# STM32F4_Schematics.net
KiCad netlist of a schematic drawn in Altium Designer
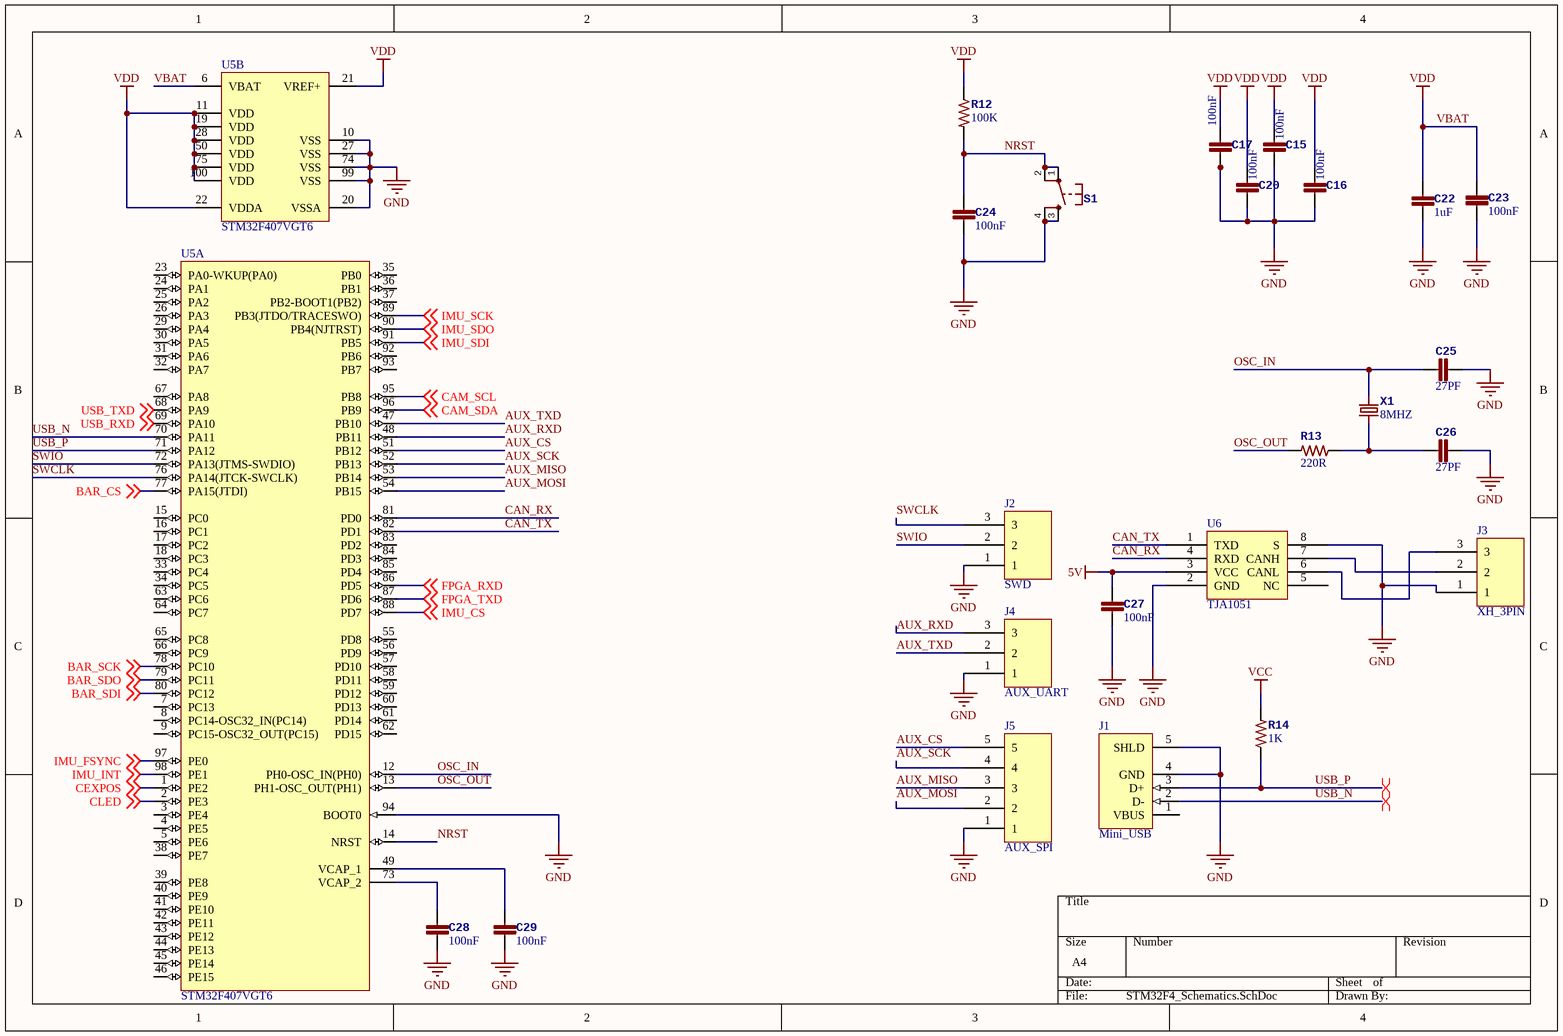
[diagram p0: STM32F4_Schematics.SchDoc]

(export (version "E")
  (design (tool "Eeschema 10.0.6"))
  (components
    (comp (ref "C15")
      (value "100nF")
      (footprint "_0805")
      (fields (field (name "Comment") "Cap"))
      (libsource (lib "") (part "Cap_1_1"))
    )
    (comp (ref "C16")
      (value "100nF")
      (footprint "_0805")
      (fields (field (name "Comment") "Cap"))
      (libsource (lib "") (part "Cap_1_1"))
    )
    (comp (ref "C17")
      (value "100nF")
      (footprint "_0805")
      (fields (field (name "Comment") "Cap"))
      (libsource (lib "") (part "Cap_1_1"))
    )
    (comp (ref "C20")
      (value "100nF")
      (footprint "_0805")
      (fields (field (name "Comment") "Cap"))
      (libsource (lib "") (part "Cap_1_1"))
    )
    (comp (ref "C22")
      (value "1uF")
      (footprint "_0805")
      (fields (field (name "Comment") "Cap"))
      (libsource (lib "") (part "Cap_1_1"))
    )
    (comp (ref "C23")
      (value "100nF")
      (footprint "_0805")
      (fields (field (name "Comment") "Cap"))
      (libsource (lib "") (part "Cap_1_1"))
    )
    (comp (ref "C24")
      (value "100nF")
      (footprint "_0805")
      (fields (field (name "Comment") "Cap"))
      (libsource (lib "") (part "Cap_1_2"))
    )
    (comp (ref "C25")
      (value "27PF")
      (footprint "_0805")
      (fields (field (name "Comment") "Cap"))
      (libsource (lib "Passives_Integrated_Library") (part "Cap_1"))
    )
    (comp (ref "C26")
      (value "27PF")
      (footprint "_0805")
      (fields (field (name "Comment") "Cap"))
      (libsource (lib "Passives_Integrated_Library") (part "Cap_1"))
    )
    (comp (ref "C27")
      (value "100nF")
      (footprint "_0805")
      (fields (field (name "Comment") "Cap"))
      (libsource (lib "") (part "Cap_1_1"))
    )
    (comp (ref "C28")
      (value "100nF")
      (footprint "_0805")
      (fields (field (name "Comment") "Cap"))
      (libsource (lib "") (part "Cap_1_1"))
    )
    (comp (ref "C29")
      (value "100nF")
      (footprint "_0805")
      (fields (field (name "Comment") "Cap"))
      (libsource (lib "") (part "Cap_1_1"))
    )
    (comp (ref "J1")
      (value "Mini_USB")
      (footprint "My_USB")
      (description "USB 2.0, Right Angle, SMT, B Type, Receptacle, 5 Position, Black")
      (fields (field (name "PUBLISHER") "Altium Limited"))
      (libsource (lib "PC_Connectors_Integrated_Library") (part "Mini_USB"))
    )
    (comp (ref "J2")
      (value "SWD")
      (footprint "XH_3PIN")
      (libsource (lib "Others_Integrated_Library") (part "XH_3PIN"))
    )
    (comp (ref "J3")
      (value "XH_3PIN")
      (footprint "XH_3PIN")
      (libsource (lib "Others_Integrated_Library") (part "XH_3PIN"))
    )
    (comp (ref "J4")
      (value "AUX_UART")
      (footprint "XH_3PIN")
      (libsource (lib "Others_Integrated_Library") (part "XH_3PIN"))
    )
    (comp (ref "J5")
      (value "AUX_SPI")
      (footprint "XH_5PIN")
      (libsource (lib "Others_Integrated_Library") (part "XH_5PIN"))
    )
    (comp (ref "R12")
      (value "100K")
      (footprint "_0603")
      (fields (field (name "Comment") "Resistor"))
      (libsource (lib "Passives_Integrated_Library") (part "Resistor"))
    )
    (comp (ref "R13")
      (value "220R")
      (footprint "_0603")
      (fields (field (name "Comment") "Resistor"))
      (libsource (lib "Passives_Integrated_Library") (part "Resistor"))
    )
    (comp (ref "R14")
      (value "1K")
      (footprint "_0603")
      (fields (field (name "Comment") "Resistor"))
      (libsource (lib "Passives_Integrated_Library") (part "Resistor"))
    )
    (comp (ref "S1")
      (value "PushButton-4Pin")
      (footprint "_TACTILE_SWITCH_PTH_6.0MM")
      (libsource (lib "Miscellaneous_Integrated_Library") (part "PushButton-4Pin"))
    )
    (comp (ref "U5")
      (value "STM32F407VGT6")
      (footprint "STM-LQFP100_N")
      (fields (field (name "MANUFACTURER") "STMicroelectronics"))
      (libsource (lib "STMicroelectronics STM32 F4") (part "STM32F407VGT6"))
    )
    (comp (ref "U6")
      (value "TJA1051")
      (footprint "SO-8N")
      (libsource (lib "Transievers_Integrated_Library") (part "TJA1051"))
    )
    (comp (ref "X1")
      (value "8MHZ")
      (footprint "_CRYSTAL-HC49UP")
      (fields (field (name "Comment") "Crystal_1"))
      (libsource (lib "Passives_Integrated_Library") (part "Crystal_1"))
    )
  )
  (nets
    (net (code "1") (name "/AUX_CS") (class "Default")
      (node (ref "J5") (pin "5") (pinfunction "5_5") (pintype "passive"))
      (node (ref "U5") (pin "51") (pinfunction "PB12_51") (pintype "bidirectional"))
    )
    (net (code "2") (name "/AUX_MISO") (class "Default")
      (node (ref "J5") (pin "3") (pinfunction "3_3") (pintype "passive"))
      (node (ref "U5") (pin "53") (pinfunction "PB14_53") (pintype "bidirectional"))
    )
    (net (code "3") (name "/AUX_MOSI") (class "Default")
      (node (ref "J5") (pin "2") (pinfunction "2_2") (pintype "passive"))
      (node (ref "U5") (pin "54") (pinfunction "PB15_54") (pintype "bidirectional"))
    )
    (net (code "4") (name "/AUX_RXD") (class "Default")
      (node (ref "J4") (pin "3") (pinfunction "3_3") (pintype "passive"))
      (node (ref "U5") (pin "48") (pinfunction "PB11_48") (pintype "bidirectional"))
    )
    (net (code "5") (name "/AUX_SCK") (class "Default")
      (node (ref "J5") (pin "4") (pinfunction "4_4") (pintype "passive"))
      (node (ref "U5") (pin "52") (pinfunction "PB13_52") (pintype "bidirectional"))
    )
    (net (code "6") (name "/AUX_TXD") (class "Default")
      (node (ref "J4") (pin "2") (pinfunction "2_2") (pintype "passive"))
      (node (ref "U5") (pin "47") (pinfunction "PB10_47") (pintype "bidirectional"))
    )
    (net (code "7") (name "/CAN_RX") (class "Default")
      (node (ref "U5") (pin "81") (pinfunction "PD0_81") (pintype "bidirectional"))
      (node (ref "U6") (pin "4") (pinfunction "RXD_4") (pintype "passive"))
    )
    (net (code "8") (name "/CAN_TX") (class "Default")
      (node (ref "U5") (pin "82") (pinfunction "PD1_82") (pintype "bidirectional"))
      (node (ref "U6") (pin "1") (pinfunction "TXD_1") (pintype "passive"))
    )
    (net (code "9") (name "/NRST") (class "Default")
      (node (ref "C24") (pin "1") (pinfunction "1_1") (pintype "passive"))
      (node (ref "R12") (pin "2") (pinfunction "2_2") (pintype "passive"))
      (node (ref "S1") (pin "1") (pinfunction "1_1") (pintype "passive"))
      (node (ref "S1") (pin "2") (pinfunction "2_2") (pintype "passive"))
      (node (ref "U5") (pin "14") (pinfunction "NRST_14") (pintype "bidirectional"))
    )
    (net (code "10") (name "/OSC_IN") (class "Default")
      (node (ref "C25") (pin "1") (pinfunction "1_1") (pintype "passive"))
      (node (ref "U5") (pin "12") (pinfunction "PH0-OSC_IN(PH0)_12") (pintype "bidirectional"))
      (node (ref "X1") (pin "2") (pinfunction "2_2") (pintype "passive"))
    )
    (net (code "11") (name "/OSC_OUT") (class "Default")
      (node (ref "R13") (pin "2") (pinfunction "2_2") (pintype "passive"))
      (node (ref "U5") (pin "13") (pinfunction "PH1-OSC_OUT(PH1)_13") (pintype "bidirectional"))
    )
    (net (code "12") (name "/SWCLK") (class "Default")
      (node (ref "J2") (pin "3") (pinfunction "3_3") (pintype "passive"))
      (node (ref "U5") (pin "76") (pinfunction "PA14(JTCK-SWCLK)_76") (pintype "bidirectional"))
    )
    (net (code "13") (name "/SWIO") (class "Default")
      (node (ref "J2") (pin "2") (pinfunction "2_2") (pintype "passive"))
      (node (ref "U5") (pin "72") (pinfunction "PA13(JTMS-SWDIO)_72") (pintype "bidirectional"))
    )
    (net (code "14") (name "/USB_N") (class "Default")
      (node (ref "J1") (pin "2") (pinfunction "D-_2") (pintype "input"))
      (node (ref "U5") (pin "70") (pinfunction "PA11_70") (pintype "bidirectional"))
    )
    (net (code "15") (name "/USB_P") (class "Default")
      (node (ref "J1") (pin "3") (pinfunction "D+_3") (pintype "input"))
      (node (ref "R14") (pin "1") (pinfunction "1_1") (pintype "passive"))
      (node (ref "U5") (pin "71") (pinfunction "PA12_71") (pintype "bidirectional"))
    )
    (net (code "16") (name "5V") (class "Default")
      (node (ref "C27") (pin "2") (pinfunction "2_2") (pintype "passive"))
      (node (ref "U6") (pin "3") (pinfunction "VCC_3") (pintype "passive"))
    )
    (net (code "17") (name "BAR_CS") (class "Default")
      (node (ref "U5") (pin "77") (pinfunction "PA15(JTDI)_77") (pintype "bidirectional"))
    )
    (net (code "18") (name "BAR_SCK") (class "Default")
      (node (ref "U5") (pin "78") (pinfunction "PC10_78") (pintype "bidirectional"))
    )
    (net (code "19") (name "BAR_SDI") (class "Default")
      (node (ref "U5") (pin "80") (pinfunction "PC12_80") (pintype "bidirectional"))
    )
    (net (code "20") (name "BAR_SDO") (class "Default")
      (node (ref "U5") (pin "79") (pinfunction "PC11_79") (pintype "bidirectional"))
    )
    (net (code "21") (name "CAM_SCL") (class "Default")
      (node (ref "U5") (pin "95") (pinfunction "PB8_95") (pintype "bidirectional"))
    )
    (net (code "22") (name "CAM_SDA") (class "Default")
      (node (ref "U5") (pin "96") (pinfunction "PB9_96") (pintype "bidirectional"))
    )
    (net (code "23") (name "CEXPOS") (class "Default")
      (node (ref "U5") (pin "1") (pinfunction "PE2_1") (pintype "bidirectional"))
    )
    (net (code "24") (name "CLED") (class "Default")
      (node (ref "U5") (pin "2") (pinfunction "PE3_2") (pintype "bidirectional"))
    )
    (net (code "25") (name "FPGA_RXD") (class "Default")
      (node (ref "U5") (pin "86") (pinfunction "PD5_86") (pintype "bidirectional"))
    )
    (net (code "26") (name "FPGA_TXD") (class "Default")
      (node (ref "U5") (pin "87") (pinfunction "PD6_87") (pintype "bidirectional"))
    )
    (net (code "27") (name "GND") (class "Default")
      (node (ref "C15") (pin "1") (pinfunction "1_1") (pintype "passive"))
      (node (ref "C16") (pin "1") (pinfunction "1_1") (pintype "passive"))
      (node (ref "C17") (pin "1") (pinfunction "1_1") (pintype "passive"))
      (node (ref "C20") (pin "1") (pinfunction "1_1") (pintype "passive"))
      (node (ref "C22") (pin "1") (pinfunction "1_1") (pintype "passive"))
      (node (ref "C23") (pin "1") (pinfunction "1_1") (pintype "passive"))
      (node (ref "C24") (pin "2") (pinfunction "2_2") (pintype "passive"))
      (node (ref "C25") (pin "2") (pinfunction "2_2") (pintype "passive"))
      (node (ref "C26") (pin "2") (pinfunction "2_2") (pintype "passive"))
      (node (ref "C27") (pin "1") (pinfunction "1_1") (pintype "passive"))
      (node (ref "C28") (pin "1") (pinfunction "1_1") (pintype "passive"))
      (node (ref "C29") (pin "1") (pinfunction "1_1") (pintype "passive"))
      (node (ref "J1") (pin "4") (pinfunction "GND_4") (pintype "power_in"))
      (node (ref "J1") (pin "5") (pinfunction "SHLD_5") (pintype "passive"))
      (node (ref "J2") (pin "1") (pinfunction "1_1") (pintype "passive"))
      (node (ref "J3") (pin "1") (pinfunction "1_1") (pintype "passive"))
      (node (ref "J4") (pin "1") (pinfunction "1_1") (pintype "passive"))
      (node (ref "J5") (pin "1") (pinfunction "1_1") (pintype "passive"))
      (node (ref "S1") (pin "3") (pinfunction "3_3") (pintype "passive"))
      (node (ref "S1") (pin "4") (pinfunction "4_4") (pintype "passive"))
      (node (ref "U5") (pin "10") (pinfunction "VSS_10") (pintype "power_in"))
      (node (ref "U5") (pin "20") (pinfunction "VSSA_20") (pintype "power_in"))
      (node (ref "U5") (pin "27") (pinfunction "VSS_27") (pintype "power_in"))
      (node (ref "U5") (pin "74") (pinfunction "VSS_74") (pintype "power_in"))
      (node (ref "U5") (pin "94") (pinfunction "BOOT0_94") (pintype "input"))
      (node (ref "U5") (pin "99") (pinfunction "VSS_99") (pintype "power_in"))
      (node (ref "U6") (pin "2") (pinfunction "GND_2") (pintype "passive"))
      (node (ref "U6") (pin "8") (pinfunction "S_8") (pintype "passive"))
    )
    (net (code "28") (name "IMU_CS") (class "Default")
      (node (ref "U5") (pin "88") (pinfunction "PD7_88") (pintype "bidirectional"))
    )
    (net (code "29") (name "IMU_FSYNC") (class "Default")
      (node (ref "U5") (pin "97") (pinfunction "PE0_97") (pintype "bidirectional"))
    )
    (net (code "30") (name "IMU_INT") (class "Default")
      (node (ref "U5") (pin "98") (pinfunction "PE1_98") (pintype "bidirectional"))
    )
    (net (code "31") (name "IMU_SCK") (class "Default")
      (node (ref "U5") (pin "89") (pinfunction "PB3(JTDO/TRACESWO)_89") (pintype "bidirectional"))
    )
    (net (code "32") (name "IMU_SDI") (class "Default")
      (node (ref "U5") (pin "91") (pinfunction "PB5_91") (pintype "bidirectional"))
    )
    (net (code "33") (name "IMU_SDO") (class "Default")
      (node (ref "U5") (pin "90") (pinfunction "PB4(NJTRST)_90") (pintype "bidirectional"))
    )
    (net (code "34") (name "Net-(C26-Pad1)") (class "Default")
      (node (ref "C26") (pin "1") (pinfunction "1_1") (pintype "passive"))
      (node (ref "R13") (pin "1") (pinfunction "1_1") (pintype "passive"))
      (node (ref "X1") (pin "1") (pinfunction "1_1") (pintype "passive"))
    )
    (net (code "35") (name "Net-(U5A-VCAP_1)") (class "Default")
      (node (ref "C29") (pin "2") (pinfunction "2_2") (pintype "passive"))
      (node (ref "U5") (pin "49") (pinfunction "VCAP_1_49") (pintype "power_in"))
    )
    (net (code "36") (name "Net-(U5A-VCAP_2)") (class "Default")
      (node (ref "C28") (pin "2") (pinfunction "2_2") (pintype "passive"))
      (node (ref "U5") (pin "73") (pinfunction "VCAP_2_73") (pintype "power_in"))
    )
    (net (code "37") (name "Net-(U6-CANH)") (class "Default")
      (node (ref "J3") (pin "2") (pinfunction "2_2") (pintype "passive"))
      (node (ref "U6") (pin "7") (pinfunction "CANH_7") (pintype "passive"))
    )
    (net (code "38") (name "Net-(U6-CANL)") (class "Default")
      (node (ref "J3") (pin "3") (pinfunction "3_3") (pintype "passive"))
      (node (ref "U6") (pin "6") (pinfunction "CANL_6") (pintype "passive"))
    )
    (net (code "39") (name "USB_RXD") (class "Default")
      (node (ref "U5") (pin "69") (pinfunction "PA10_69") (pintype "bidirectional"))
    )
    (net (code "40") (name "USB_TXD") (class "Default")
      (node (ref "U5") (pin "68") (pinfunction "PA9_68") (pintype "bidirectional"))
    )
    (net (code "41") (name "VCC") (class "Default")
      (node (ref "R14") (pin "2") (pinfunction "2_2") (pintype "passive"))
    )
    (net (code "42") (name "VDD") (class "Default")
      (node (ref "C15") (pin "2") (pinfunction "2_2") (pintype "passive"))
      (node (ref "C16") (pin "2") (pinfunction "2_2") (pintype "passive"))
      (node (ref "C17") (pin "2") (pinfunction "2_2") (pintype "passive"))
      (node (ref "C20") (pin "2") (pinfunction "2_2") (pintype "passive"))
      (node (ref "C22") (pin "2") (pinfunction "2_2") (pintype "passive"))
      (node (ref "C23") (pin "2") (pinfunction "2_2") (pintype "passive"))
      (node (ref "R12") (pin "1") (pinfunction "1_1") (pintype "passive"))
      (node (ref "U5") (pin "100") (pinfunction "VDD_100") (pintype "power_in"))
      (node (ref "U5") (pin "11") (pinfunction "VDD_11") (pintype "power_in"))
      (node (ref "U5") (pin "19") (pinfunction "VDD_19") (pintype "power_in"))
      (node (ref "U5") (pin "21") (pinfunction "VREF+_21") (pintype "power_in"))
      (node (ref "U5") (pin "22") (pinfunction "VDDA_22") (pintype "power_in"))
      (node (ref "U5") (pin "28") (pinfunction "VDD_28") (pintype "power_in"))
      (node (ref "U5") (pin "50") (pinfunction "VDD_50") (pintype "power_in"))
      (node (ref "U5") (pin "6") (pinfunction "VBAT_6") (pintype "power_in"))
      (node (ref "U5") (pin "75") (pinfunction "VDD_75") (pintype "power_in"))
    )
    (net (code "43") (name "unconnected-(J1-VBUS-Pad1)") (class "Default")
      (node (ref "J1") (pin "1") (pinfunction "VBUS_1") (pintype "power_in"))
    )
    (net (code "44") (name "unconnected-(U5A-PA0-WKUP(PA0)-Pad23)") (class "Default")
      (node (ref "U5") (pin "23") (pinfunction "PA0-WKUP(PA0)_23") (pintype "bidirectional"))
    )
    (net (code "45") (name "unconnected-(U5A-PA1-Pad24)") (class "Default")
      (node (ref "U5") (pin "24") (pinfunction "PA1_24") (pintype "bidirectional"))
    )
    (net (code "46") (name "unconnected-(U5A-PA2-Pad25)") (class "Default")
      (node (ref "U5") (pin "25") (pinfunction "PA2_25") (pintype "bidirectional"))
    )
    (net (code "47") (name "unconnected-(U5A-PA3-Pad26)") (class "Default")
      (node (ref "U5") (pin "26") (pinfunction "PA3_26") (pintype "bidirectional"))
    )
    (net (code "48") (name "unconnected-(U5A-PA4-Pad29)") (class "Default")
      (node (ref "U5") (pin "29") (pinfunction "PA4_29") (pintype "bidirectional"))
    )
    (net (code "49") (name "unconnected-(U5A-PA5-Pad30)") (class "Default")
      (node (ref "U5") (pin "30") (pinfunction "PA5_30") (pintype "bidirectional"))
    )
    (net (code "50") (name "unconnected-(U5A-PA6-Pad31)") (class "Default")
      (node (ref "U5") (pin "31") (pinfunction "PA6_31") (pintype "bidirectional"))
    )
    (net (code "51") (name "unconnected-(U5A-PA7-Pad32)") (class "Default")
      (node (ref "U5") (pin "32") (pinfunction "PA7_32") (pintype "bidirectional"))
    )
    (net (code "52") (name "unconnected-(U5A-PA8-Pad67)") (class "Default")
      (node (ref "U5") (pin "67") (pinfunction "PA8_67") (pintype "bidirectional"))
    )
    (net (code "53") (name "unconnected-(U5A-PB0-Pad35)") (class "Default")
      (node (ref "U5") (pin "35") (pinfunction "PB0_35") (pintype "bidirectional"))
    )
    (net (code "54") (name "unconnected-(U5A-PB1-Pad36)") (class "Default")
      (node (ref "U5") (pin "36") (pinfunction "PB1_36") (pintype "bidirectional"))
    )
    (net (code "55") (name "unconnected-(U5A-PB2-BOOT1(PB2)-Pad37)") (class "Default")
      (node (ref "U5") (pin "37") (pinfunction "PB2-BOOT1(PB2)_37") (pintype "bidirectional"))
    )
    (net (code "56") (name "unconnected-(U5A-PB6-Pad92)") (class "Default")
      (node (ref "U5") (pin "92") (pinfunction "PB6_92") (pintype "bidirectional"))
    )
    (net (code "57") (name "unconnected-(U5A-PB7-Pad93)") (class "Default")
      (node (ref "U5") (pin "93") (pinfunction "PB7_93") (pintype "bidirectional"))
    )
    (net (code "58") (name "unconnected-(U5A-PC0-Pad15)") (class "Default")
      (node (ref "U5") (pin "15") (pinfunction "PC0_15") (pintype "bidirectional"))
    )
    (net (code "59") (name "unconnected-(U5A-PC1-Pad16)") (class "Default")
      (node (ref "U5") (pin "16") (pinfunction "PC1_16") (pintype "bidirectional"))
    )
    (net (code "60") (name "unconnected-(U5A-PC2-Pad17)") (class "Default")
      (node (ref "U5") (pin "17") (pinfunction "PC2_17") (pintype "bidirectional"))
    )
    (net (code "61") (name "unconnected-(U5A-PC3-Pad18)") (class "Default")
      (node (ref "U5") (pin "18") (pinfunction "PC3_18") (pintype "bidirectional"))
    )
    (net (code "62") (name "unconnected-(U5A-PC4-Pad33)") (class "Default")
      (node (ref "U5") (pin "33") (pinfunction "PC4_33") (pintype "bidirectional"))
    )
    (net (code "63") (name "unconnected-(U5A-PC5-Pad34)") (class "Default")
      (node (ref "U5") (pin "34") (pinfunction "PC5_34") (pintype "bidirectional"))
    )
    (net (code "64") (name "unconnected-(U5A-PC6-Pad63)") (class "Default")
      (node (ref "U5") (pin "63") (pinfunction "PC6_63") (pintype "bidirectional"))
    )
    (net (code "65") (name "unconnected-(U5A-PC7-Pad64)") (class "Default")
      (node (ref "U5") (pin "64") (pinfunction "PC7_64") (pintype "bidirectional"))
    )
    (net (code "66") (name "unconnected-(U5A-PC8-Pad65)") (class "Default")
      (node (ref "U5") (pin "65") (pinfunction "PC8_65") (pintype "bidirectional"))
    )
    (net (code "67") (name "unconnected-(U5A-PC9-Pad66)") (class "Default")
      (node (ref "U5") (pin "66") (pinfunction "PC9_66") (pintype "bidirectional"))
    )
    (net (code "68") (name "unconnected-(U5A-PC13-Pad7)") (class "Default")
      (node (ref "U5") (pin "7") (pinfunction "PC13_7") (pintype "bidirectional"))
    )
    (net (code "69") (name "unconnected-(U5A-PC14-OSC32_IN(PC14)-Pad8)") (class "Default")
      (node (ref "U5") (pin "8") (pinfunction "PC14-OSC32_IN(PC14)_8") (pintype "bidirectional"))
    )
    (net (code "70") (name "unconnected-(U5A-PC15-OSC32_OUT(PC15)-Pad9)") (class "Default")
      (node (ref "U5") (pin "9") (pinfunction "PC15-OSC32_OUT(PC15)_9") (pintype "bidirectional"))
    )
    (net (code "71") (name "unconnected-(U5A-PD2-Pad83)") (class "Default")
      (node (ref "U5") (pin "83") (pinfunction "PD2_83") (pintype "bidirectional"))
    )
    (net (code "72") (name "unconnected-(U5A-PD3-Pad84)") (class "Default")
      (node (ref "U5") (pin "84") (pinfunction "PD3_84") (pintype "bidirectional"))
    )
    (net (code "73") (name "unconnected-(U5A-PD4-Pad85)") (class "Default")
      (node (ref "U5") (pin "85") (pinfunction "PD4_85") (pintype "bidirectional"))
    )
    (net (code "74") (name "unconnected-(U5A-PD8-Pad55)") (class "Default")
      (node (ref "U5") (pin "55") (pinfunction "PD8_55") (pintype "bidirectional"))
    )
    (net (code "75") (name "unconnected-(U5A-PD9-Pad56)") (class "Default")
      (node (ref "U5") (pin "56") (pinfunction "PD9_56") (pintype "bidirectional"))
    )
    (net (code "76") (name "unconnected-(U5A-PD10-Pad57)") (class "Default")
      (node (ref "U5") (pin "57") (pinfunction "PD10_57") (pintype "bidirectional"))
    )
    (net (code "77") (name "unconnected-(U5A-PD11-Pad58)") (class "Default")
      (node (ref "U5") (pin "58") (pinfunction "PD11_58") (pintype "bidirectional"))
    )
    (net (code "78") (name "unconnected-(U5A-PD12-Pad59)") (class "Default")
      (node (ref "U5") (pin "59") (pinfunction "PD12_59") (pintype "bidirectional"))
    )
    (net (code "79") (name "unconnected-(U5A-PD13-Pad60)") (class "Default")
      (node (ref "U5") (pin "60") (pinfunction "PD13_60") (pintype "bidirectional"))
    )
    (net (code "80") (name "unconnected-(U5A-PD14-Pad61)") (class "Default")
      (node (ref "U5") (pin "61") (pinfunction "PD14_61") (pintype "bidirectional"))
    )
    (net (code "81") (name "unconnected-(U5A-PD15-Pad62)") (class "Default")
      (node (ref "U5") (pin "62") (pinfunction "PD15_62") (pintype "bidirectional"))
    )
    (net (code "82") (name "unconnected-(U5A-PE4-Pad3)") (class "Default")
      (node (ref "U5") (pin "3") (pinfunction "PE4_3") (pintype "bidirectional"))
    )
    (net (code "83") (name "unconnected-(U5A-PE5-Pad4)") (class "Default")
      (node (ref "U5") (pin "4") (pinfunction "PE5_4") (pintype "bidirectional"))
    )
    (net (code "84") (name "unconnected-(U5A-PE6-Pad5)") (class "Default")
      (node (ref "U5") (pin "5") (pinfunction "PE6_5") (pintype "bidirectional"))
    )
    (net (code "85") (name "unconnected-(U5A-PE7-Pad38)") (class "Default")
      (node (ref "U5") (pin "38") (pinfunction "PE7_38") (pintype "bidirectional"))
    )
    (net (code "86") (name "unconnected-(U5A-PE8-Pad39)") (class "Default")
      (node (ref "U5") (pin "39") (pinfunction "PE8_39") (pintype "bidirectional"))
    )
    (net (code "87") (name "unconnected-(U5A-PE9-Pad40)") (class "Default")
      (node (ref "U5") (pin "40") (pinfunction "PE9_40") (pintype "bidirectional"))
    )
    (net (code "88") (name "unconnected-(U5A-PE10-Pad41)") (class "Default")
      (node (ref "U5") (pin "41") (pinfunction "PE10_41") (pintype "bidirectional"))
    )
    (net (code "89") (name "unconnected-(U5A-PE11-Pad42)") (class "Default")
      (node (ref "U5") (pin "42") (pinfunction "PE11_42") (pintype "bidirectional"))
    )
    (net (code "90") (name "unconnected-(U5A-PE12-Pad43)") (class "Default")
      (node (ref "U5") (pin "43") (pinfunction "PE12_43") (pintype "bidirectional"))
    )
    (net (code "91") (name "unconnected-(U5A-PE13-Pad44)") (class "Default")
      (node (ref "U5") (pin "44") (pinfunction "PE13_44") (pintype "bidirectional"))
    )
    (net (code "92") (name "unconnected-(U5A-PE14-Pad45)") (class "Default")
      (node (ref "U5") (pin "45") (pinfunction "PE14_45") (pintype "bidirectional"))
    )
    (net (code "93") (name "unconnected-(U5A-PE15-Pad46)") (class "Default")
      (node (ref "U5") (pin "46") (pinfunction "PE15_46") (pintype "bidirectional"))
    )
    (net (code "94") (name "unconnected-(U6-NC-Pad5)") (class "Default")
      (node (ref "U6") (pin "5") (pinfunction "NC_5") (pintype "passive"))
    )
  )
)
